# OLED0_96.net
KiCad netlist of a schematic drawn in Altium Designer
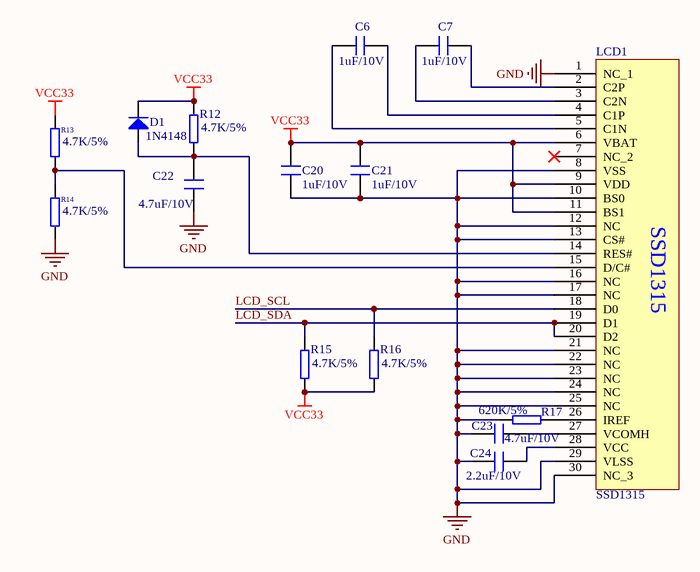
[diagram p0: OLED0.96.SchDoc]

(export (version "E")
  (design (tool "Eeschema 10.0.6"))
  (components
    (comp (ref "C6") (value "1uF/10V") (footprint "0603R") (libsource (lib "ES_Schematic") (part "CAP")))
    (comp (ref "C7") (value "1uF/10V") (footprint "0603R") (libsource (lib "ES_Schematic") (part "CAP")))
    (comp (ref "C20") (value "1uF/10V") (footprint "0603R") (libsource (lib "ES_Schematic") (part "CAP")))
    (comp (ref "C21") (value "1uF/10V") (footprint "0603R") (libsource (lib "ES_Schematic") (part "CAP")))
    (comp (ref "C22") (value "4.7uF/10V") (footprint "0603R") (libsource (lib "ES_Schematic") (part "CAP")))
    (comp (ref "C23") (value "4.7uF/10V") (footprint "0603R") (libsource (lib "ES_Schematic") (part "CAP")))
    (comp (ref "C24") (value "2.2uF/10V") (footprint "0603R") (libsource (lib "ES_Schematic") (part "CAP")))
    (comp (ref "D1") (value "1N4148") (footprint "1206D") (libsource (lib "ES_Schematic") (part "DIODE")))
    (comp (ref "LCD1")
      (value "SSD1315")
      (footprint "OLED0.96 丝印")
      (libsource (lib "sangjian") (part "SSD1315"))
    )
    (comp (ref "R12") (value "4.7K/5%") (footprint "0603R") (libsource (lib "ES_Schematic") (part "RES")))
    (comp (ref "R13") (value "4.7K/5%") (footprint "0603R") (libsource (lib "ES_Schematic") (part "RES")))
    (comp (ref "R14") (value "4.7K/5%") (footprint "0603R") (libsource (lib "ES_Schematic") (part "RES")))
    (comp (ref "R15") (value "4.7K/5%") (footprint "0603R") (libsource (lib "ES_Schematic") (part "RES")))
    (comp (ref "R16") (value "4.7K/5%") (footprint "0603R") (libsource (lib "ES_Schematic") (part "RES")))
    (comp (ref "R17") (value "620K/5%") (footprint "0603R") (libsource (lib "ES_Schematic") (part "RES")))
  )
  (nets
    (net (code "1") (name "/LCD_SCL") (class "Default")
      (node (ref "LCD1") (pin "18") (pinfunction "D0_18") (pintype "passive"))
      (node (ref "R16") (pin "1") (pinfunction "1_1") (pintype "passive"))
    )
    (net (code "2") (name "/LCD_SDA") (class "Default")
      (node (ref "LCD1") (pin "19") (pinfunction "D1_19") (pintype "passive"))
      (node (ref "LCD1") (pin "20") (pinfunction "D2_20") (pintype "passive"))
      (node (ref "R15") (pin "1") (pinfunction "1_1") (pintype "passive"))
    )
    (net (code "3") (name "GND") (class "Default")
      (node (ref "C20") (pin "1") (pinfunction "1_1") (pintype "passive"))
      (node (ref "C21") (pin "1") (pinfunction "1_1") (pintype "passive"))
      (node (ref "C22") (pin "1") (pinfunction "1_1") (pintype "passive"))
      (node (ref "C23") (pin "2") (pinfunction "2_2") (pintype "passive"))
      (node (ref "C24") (pin "2") (pinfunction "2_2") (pintype "passive"))
      (node (ref "LCD1") (pin "1") (pinfunction "NC_1_1") (pintype "passive"))
      (node (ref "LCD1") (pin "10") (pinfunction "BS0_10") (pintype "passive"))
      (node (ref "LCD1") (pin "12") (pinfunction "NC_12") (pintype "passive"))
      (node (ref "LCD1") (pin "13") (pinfunction "CS#_13") (pintype "passive"))
      (node (ref "LCD1") (pin "16") (pinfunction "NC_16") (pintype "passive"))
      (node (ref "LCD1") (pin "17") (pinfunction "NC_17") (pintype "passive"))
      (node (ref "LCD1") (pin "21") (pinfunction "NC_21") (pintype "passive"))
      (node (ref "LCD1") (pin "22") (pinfunction "NC_22") (pintype "passive"))
      (node (ref "LCD1") (pin "23") (pinfunction "NC_23") (pintype "passive"))
      (node (ref "LCD1") (pin "24") (pinfunction "NC_24") (pintype "passive"))
      (node (ref "LCD1") (pin "25") (pinfunction "NC_25") (pintype "passive"))
      (node (ref "LCD1") (pin "29") (pinfunction "VLSS_29") (pintype "passive"))
      (node (ref "LCD1") (pin "30") (pinfunction "NC_3_30") (pintype "passive"))
      (node (ref "LCD1") (pin "8") (pinfunction "VSS_8") (pintype "passive"))
      (node (ref "R14") (pin "2") (pinfunction "2_2") (pintype "passive"))
      (node (ref "R17") (pin "1") (pinfunction "1_1") (pintype "passive"))
    )
    (net (code "4") (name "Net-(D1-A)") (class "Default")
      (node (ref "C22") (pin "2") (pinfunction "2_2") (pintype "passive"))
      (node (ref "D1") (pin "2") (pinfunction "A_2") (pintype "passive"))
      (node (ref "LCD1") (pin "14") (pinfunction "RES#_14") (pintype "passive"))
      (node (ref "R12") (pin "2") (pinfunction "2_2") (pintype "passive"))
    )
    (net (code "5") (name "Net-(LCD1-C1N)") (class "Default")
      (node (ref "C6") (pin "1") (pinfunction "1_1") (pintype "passive"))
      (node (ref "LCD1") (pin "5") (pinfunction "C1N_5") (pintype "passive"))
    )
    (net (code "6") (name "Net-(LCD1-C1P)") (class "Default")
      (node (ref "C6") (pin "2") (pinfunction "2_2") (pintype "passive"))
      (node (ref "LCD1") (pin "4") (pinfunction "C1P_4") (pintype "passive"))
    )
    (net (code "7") (name "Net-(LCD1-C2N)") (class "Default")
      (node (ref "C7") (pin "1") (pinfunction "1_1") (pintype "passive"))
      (node (ref "LCD1") (pin "3") (pinfunction "C2N_3") (pintype "passive"))
    )
    (net (code "8") (name "Net-(LCD1-C2P)") (class "Default")
      (node (ref "C7") (pin "2") (pinfunction "2_2") (pintype "passive"))
      (node (ref "LCD1") (pin "2") (pinfunction "C2P_2") (pintype "passive"))
    )
    (net (code "9") (name "Net-(LCD1-D{slash}C#)") (class "Default")
      (node (ref "LCD1") (pin "15") (pinfunction "D/C#_15") (pintype "passive"))
      (node (ref "R13") (pin "2") (pinfunction "2_2") (pintype "passive"))
      (node (ref "R14") (pin "1") (pinfunction "1_1") (pintype "passive"))
    )
    (net (code "10") (name "Net-(LCD1-IREF)") (class "Default")
      (node (ref "LCD1") (pin "26") (pinfunction "IREF_26") (pintype "passive"))
      (node (ref "R17") (pin "2") (pinfunction "2_2") (pintype "passive"))
    )
    (net (code "11") (name "Net-(LCD1-VCC)") (class "Default")
      (node (ref "C24") (pin "1") (pinfunction "1_1") (pintype "passive"))
      (node (ref "LCD1") (pin "28") (pinfunction "VCC_28") (pintype "passive"))
    )
    (net (code "12") (name "Net-(LCD1-VCOMH)") (class "Default")
      (node (ref "C23") (pin "1") (pinfunction "1_1") (pintype "passive"))
      (node (ref "LCD1") (pin "27") (pinfunction "VCOMH_27") (pintype "passive"))
    )
    (net (code "13") (name "VCC33") (class "Default")
      (node (ref "C20") (pin "2") (pinfunction "2_2") (pintype "passive"))
      (node (ref "C21") (pin "2") (pinfunction "2_2") (pintype "passive"))
      (node (ref "D1") (pin "1") (pinfunction "K_1") (pintype "passive"))
      (node (ref "LCD1") (pin "11") (pinfunction "BS1_11") (pintype "passive"))
      (node (ref "LCD1") (pin "6") (pinfunction "VBAT_6") (pintype "passive"))
      (node (ref "LCD1") (pin "9") (pinfunction "VDD_9") (pintype "passive"))
      (node (ref "R12") (pin "1") (pinfunction "1_1") (pintype "passive"))
      (node (ref "R13") (pin "1") (pinfunction "1_1") (pintype "passive"))
      (node (ref "R15") (pin "2") (pinfunction "2_2") (pintype "passive"))
      (node (ref "R16") (pin "2") (pinfunction "2_2") (pintype "passive"))
    )
    (net (code "14") (name "unconnected-(LCD1-NC_2-Pad7)") (class "Default")
      (node (ref "LCD1") (pin "7") (pinfunction "NC_2_7") (pintype "passive+no_connect"))
    )
  )
)
